# hydrogen_sensors_board_v3.net
KiCad netlist of a schematic drawn in EAGLE
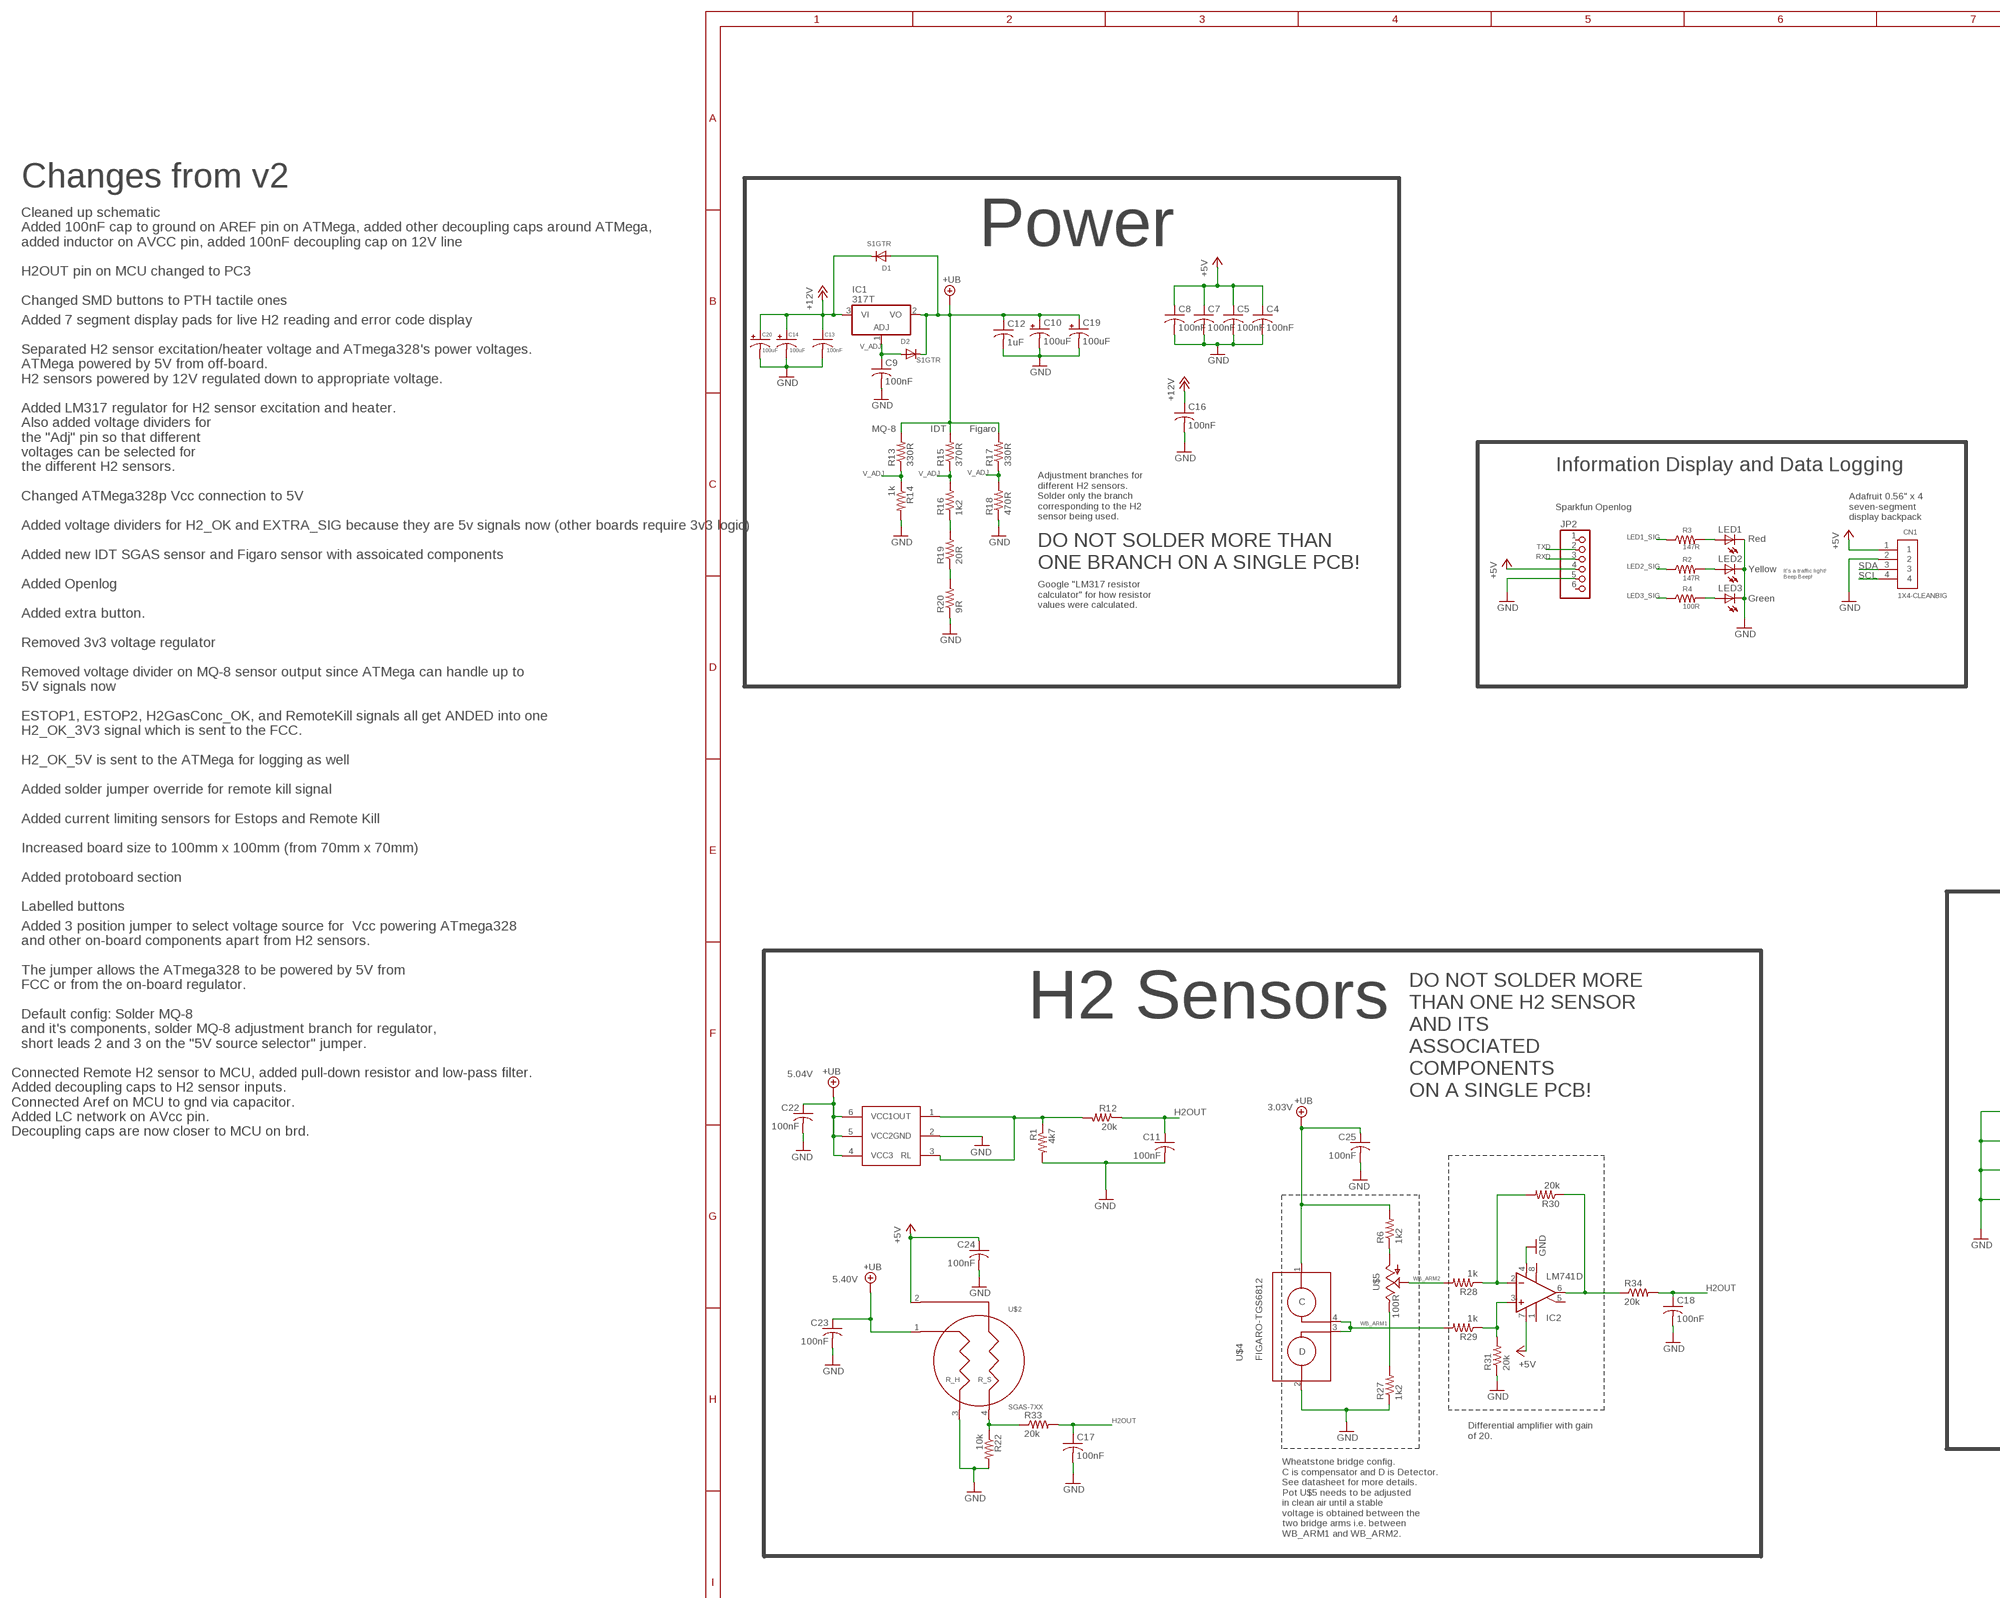
[diagram p0: schematic, sheet 1, part 1 of 2]
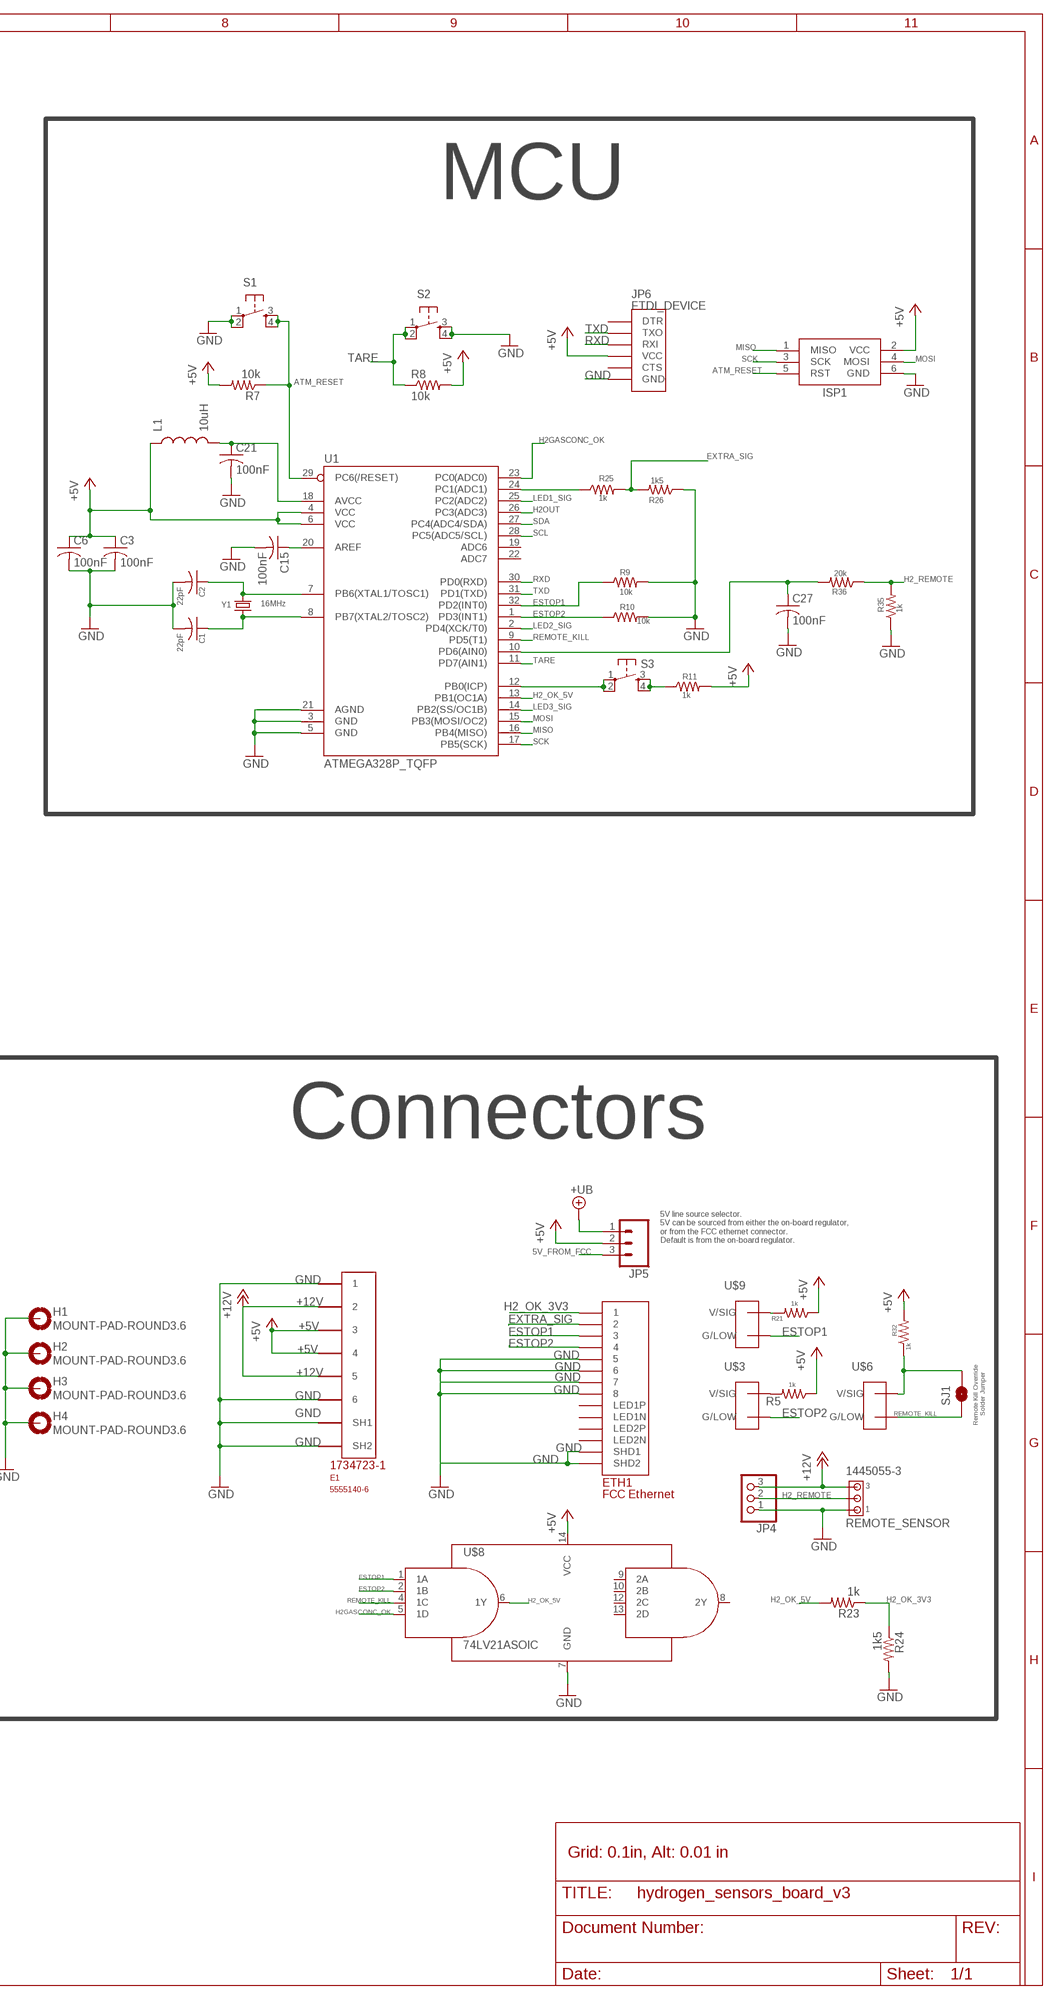
[diagram p1: schematic, sheet 1, part 2 of 2]

(export (version "E")
  (design (tool "Eeschema 10.0.6"))
  (components
    (comp (ref "C1")
      (value "22pF")
      (footprint "eagle-import:C0603K")
      (libsource (lib "eagle-import") (part "C-USC0603K"))
    )
    (comp (ref "C2")
      (value "22pF")
      (footprint "eagle-import:C0603K")
      (libsource (lib "eagle-import") (part "C-USC0603K"))
    )
    (comp (ref "C3")
      (value "100nF")
      (footprint "eagle-import:C0603")
      (libsource (lib "eagle-import") (part "C-USC0603"))
    )
    (comp (ref "C4")
      (value "100nF")
      (footprint "eagle-import:C0603")
      (libsource (lib "eagle-import") (part "C-USC0603"))
    )
    (comp (ref "C5")
      (value "100nF")
      (footprint "eagle-import:C0603")
      (libsource (lib "eagle-import") (part "C-USC0603"))
    )
    (comp (ref "C6")
      (value "100nF")
      (footprint "eagle-import:C0603")
      (libsource (lib "eagle-import") (part "C-USC0603"))
    )
    (comp (ref "C7")
      (value "100nF")
      (footprint "eagle-import:C0603")
      (libsource (lib "eagle-import") (part "C-USC0603"))
    )
    (comp (ref "C8")
      (value "100nF")
      (footprint "eagle-import:C0603")
      (libsource (lib "eagle-import") (part "C-USC0603"))
    )
    (comp (ref "C9")
      (value "100nF")
      (footprint "eagle-import:C0603")
      (libsource (lib "eagle-import") (part "C-USC0603"))
    )
    (comp (ref "C10")
      (value "100uF")
      (footprint "eagle-import:B_3528-21R")
      (libsource (lib "eagle-import") (part "CPOL-USB/3528-21R"))
    )
    (comp (ref "C11")
      (value "100nF")
      (footprint "eagle-import:C0603")
      (libsource (lib "eagle-import") (part "C-USC0603"))
    )
    (comp (ref "C12")
      (value "1uF")
      (footprint "eagle-import:C0603")
      (libsource (lib "eagle-import") (part "C-USC0603"))
    )
    (comp (ref "C13")
      (value "100nF")
      (footprint "eagle-import:C0603")
      (libsource (lib "eagle-import") (part "C-USC0603"))
    )
    (comp (ref "C14")
      (value "100uF")
      (footprint "eagle-import:B_3528-21R")
      (libsource (lib "eagle-import") (part "CPOL-USB/3528-21R"))
    )
    (comp (ref "C15")
      (value "100nF")
      (footprint "eagle-import:C0603")
      (libsource (lib "eagle-import") (part "C-USC0603"))
    )
    (comp (ref "C16")
      (value "100nF")
      (footprint "eagle-import:C0603")
      (libsource (lib "eagle-import") (part "C-USC0603"))
    )
    (comp (ref "C17")
      (value "100nF")
      (footprint "eagle-import:C0603")
      (libsource (lib "eagle-import") (part "C-USC0603"))
    )
    (comp (ref "C18")
      (value "100nF")
      (footprint "eagle-import:C0603")
      (libsource (lib "eagle-import") (part "C-USC0603"))
    )
    (comp (ref "C19")
      (value "100uF")
      (footprint "eagle-import:CPOL-RADIAL-100UF-25V")
      (libsource (lib "eagle-import") (part "CAP_POLPTH1"))
    )
    (comp (ref "C20")
      (value "100uF")
      (footprint "eagle-import:CPOL-RADIAL-100UF-25V")
      (libsource (lib "eagle-import") (part "CAP_POLPTH1"))
    )
    (comp (ref "C21")
      (value "100nF")
      (footprint "eagle-import:C0603")
      (libsource (lib "eagle-import") (part "C-USC0603"))
    )
    (comp (ref "C22")
      (value "100nF")
      (footprint "eagle-import:C0603")
      (libsource (lib "eagle-import") (part "C-USC0603"))
    )
    (comp (ref "C23")
      (value "100nF")
      (footprint "eagle-import:C0603")
      (libsource (lib "eagle-import") (part "C-USC0603"))
    )
    (comp (ref "C24")
      (value "100nF")
      (footprint "eagle-import:C0603")
      (libsource (lib "eagle-import") (part "C-USC0603"))
    )
    (comp (ref "C25")
      (value "100nF")
      (footprint "eagle-import:C0603")
      (libsource (lib "eagle-import") (part "C-USC0603"))
    )
    (comp (ref "C27")
      (value "100nF")
      (footprint "eagle-import:C0603")
      (libsource (lib "eagle-import") (part "C-USC0603"))
    )
    (comp (ref "CN1")
      (value "1X4-CLEANBIG")
      (footprint "eagle-import:1X04-CLEANBIG")
      (libsource (lib "eagle-import") (part "1X4-CLEANBIG"))
    )
    (comp (ref "D1")
      (value "S1GTR")
      (footprint "eagle-import:SMADIODE")
      (libsource (lib "eagle-import") (part "DIODESMA"))
    )
    (comp (ref "D2")
      (value "S1GTR")
      (footprint "eagle-import:SMADIODE")
      (libsource (lib "eagle-import") (part "DIODESMA"))
    )
    (comp (ref "E1")
      (value "5555140-6")
      (footprint "eagle-import:1734723-1_RJ11")
      (libsource (lib "eagle-import") (part "5555140-6"))
    )
    (comp (ref "ETH1")
      (value "FCC Ethernet")
      (footprint "eagle-import:A122645-ND")
      (libsource (lib "eagle-import") (part "ETHERNET"))
    )
    (comp (ref "H1")
      (value "MOUNT-PAD-ROUND3.6")
      (footprint "eagle-import:3,6-PAD")
      (libsource (lib "eagle-import") (part "MOUNT-PAD-ROUND3.6"))
    )
    (comp (ref "H2")
      (value "MOUNT-PAD-ROUND3.6")
      (footprint "eagle-import:3,6-PAD")
      (libsource (lib "eagle-import") (part "MOUNT-PAD-ROUND3.6"))
    )
    (comp (ref "H3")
      (value "MOUNT-PAD-ROUND3.6")
      (footprint "eagle-import:3,6-PAD")
      (libsource (lib "eagle-import") (part "MOUNT-PAD-ROUND3.6"))
    )
    (comp (ref "H4")
      (value "MOUNT-PAD-ROUND3.6")
      (footprint "eagle-import:3,6-PAD")
      (libsource (lib "eagle-import") (part "MOUNT-PAD-ROUND3.6"))
    )
    (comp (ref "IC1")
      (value "317T")
      (footprint "eagle-import:TO220H")
      (libsource (lib "eagle-import") (part "317T"))
    )
    (comp (ref "IC2")
      (value "LM741D")
      (footprint "eagle-import:SO08")
      (libsource (lib "eagle-import") (part "741DLM"))
    )
    (comp (ref "ISP1")
      (value "AVRISP-BOX")
      (footprint "eagle-import:AVRISP-BOX")
      (libsource (lib "eagle-import") (part "AVRISP-BOX"))
    )
    (comp (ref "JP2")
      (value "PINHD-1X6LOCK")
      (footprint "eagle-import:1X06-BIGLOCK")
      (libsource (lib "eagle-import") (part "PINHD-1X6LOCK"))
    )
    (comp (ref "JP4")
      (value "PINHD-1X3")
      (footprint "eagle-import:1X03")
      (libsource (lib "eagle-import") (part "PINHD-1X3"))
    )
    (comp (ref "JP5")
      (value "M03PTH")
      (footprint "eagle-import:1X03")
      (libsource (lib "eagle-import") (part "M03PTH"))
    )
    (comp (ref "JP6")
      (value "FTDI_DEVICE")
      (footprint "eagle-import:FTDI_DEVICE_SIDE")
      (libsource (lib "eagle-import") (part "FTDI_DEVICE"))
    )
    (comp (ref "L1")
      (value "10uH")
      (footprint "eagle-import:0603")
      (libsource (lib "eagle-import") (part "INDUCTOR0603"))
    )
    (comp (ref "LED1")
      (value "Red")
      (footprint "eagle-import:CHIPLED_0805")
      (libsource (lib "eagle-import") (part "LEDCHIPLED_0805"))
    )
    (comp (ref "LED2")
      (value "Yellow")
      (footprint "eagle-import:CHIPLED_0805")
      (libsource (lib "eagle-import") (part "LEDCHIPLED_0805"))
    )
    (comp (ref "LED3")
      (value "Green")
      (footprint "eagle-import:CHIPLED_0805")
      (libsource (lib "eagle-import") (part "LEDCHIPLED_0805"))
    )
    (comp (ref "R1")
      (value "4k7")
      (footprint "eagle-import:0603-RES")
      (libsource (lib "eagle-import") (part "RESISTOR0603-RES"))
    )
    (comp (ref "R2")
      (value "147R")
      (footprint "eagle-import:0603-RES")
      (libsource (lib "eagle-import") (part "SparkFun-Resistors_RESISTOR0603-RES"))
    )
    (comp (ref "R3")
      (value "147R")
      (footprint "eagle-import:0603-RES")
      (libsource (lib "eagle-import") (part "SparkFun-Resistors_RESISTOR0603-RES"))
    )
    (comp (ref "R4")
      (value "100R")
      (footprint "eagle-import:0603-RES")
      (libsource (lib "eagle-import") (part "SparkFun-Resistors_RESISTOR0603-RES"))
    )
    (comp (ref "R5")
      (value "1k")
      (footprint "eagle-import:0603-RES")
      (libsource (lib "eagle-import") (part "RESISTOR0603-RES"))
    )
    (comp (ref "R6")
      (value "1k2")
      (footprint "eagle-import:0603-RES")
      (libsource (lib "eagle-import") (part "RESISTOR0603-RES"))
    )
    (comp (ref "R7")
      (value "10k")
      (footprint "eagle-import:0603-RES")
      (libsource (lib "eagle-import") (part "SparkFun-Resistors_RESISTOR0603-RES"))
    )
    (comp (ref "R8")
      (value "10k")
      (footprint "eagle-import:0603-RES")
      (libsource (lib "eagle-import") (part "SparkFun-Resistors_RESISTOR0603-RES"))
    )
    (comp (ref "R9")
      (value "10k")
      (footprint "eagle-import:0603-RES")
      (libsource (lib "eagle-import") (part "RESISTOR0603-RES"))
    )
    (comp (ref "R10")
      (value "10k")
      (footprint "eagle-import:0603-RES")
      (libsource (lib "eagle-import") (part "RESISTOR0603-RES"))
    )
    (comp (ref "R11")
      (value "1k")
      (footprint "eagle-import:0603-RES")
      (libsource (lib "eagle-import") (part "RESISTOR0603-RES"))
    )
    (comp (ref "R12")
      (value "20k")
      (footprint "eagle-import:0603-RES")
      (libsource (lib "eagle-import") (part "RESISTOR0603-RES"))
    )
    (comp (ref "R13")
      (value "330R")
      (footprint "eagle-import:0603-RES")
      (libsource (lib "eagle-import") (part "SparkFun-Resistors_RESISTOR0603-RES"))
    )
    (comp (ref "R14")
      (value "1k")
      (footprint "eagle-import:0603-RES")
      (libsource (lib "eagle-import") (part "SparkFun-Resistors_RESISTOR0603-RES"))
    )
    (comp (ref "R15")
      (value "370R")
      (footprint "eagle-import:0603-RES")
      (libsource (lib "eagle-import") (part "SparkFun-Resistors_RESISTOR0603-RES"))
    )
    (comp (ref "R16")
      (value "1k2")
      (footprint "eagle-import:0603-RES")
      (libsource (lib "eagle-import") (part "SparkFun-Resistors_RESISTOR0603-RES"))
    )
    (comp (ref "R17")
      (value "330R")
      (footprint "eagle-import:0603-RES")
      (libsource (lib "eagle-import") (part "SparkFun-Resistors_RESISTOR0603-RES"))
    )
    (comp (ref "R18")
      (value "470R")
      (footprint "eagle-import:0603-RES")
      (libsource (lib "eagle-import") (part "SparkFun-Resistors_RESISTOR0603-RES"))
    )
    (comp (ref "R19")
      (value "20R")
      (footprint "eagle-import:0603-RES")
      (libsource (lib "eagle-import") (part "SparkFun-Resistors_RESISTOR0603-RES"))
    )
    (comp (ref "R20")
      (value "9R")
      (footprint "eagle-import:0603-RES")
      (libsource (lib "eagle-import") (part "SparkFun-Resistors_RESISTOR0603-RES"))
    )
    (comp (ref "R21")
      (value "1k")
      (footprint "eagle-import:0603-RES")
      (libsource (lib "eagle-import") (part "RESISTOR0603-RES"))
    )
    (comp (ref "R22")
      (value "10k")
      (footprint "eagle-import:0603-RES")
      (libsource (lib "eagle-import") (part "RESISTOR0603-RES"))
    )
    (comp (ref "R23")
      (value "1k")
      (footprint "eagle-import:0603-RES")
      (libsource (lib "eagle-import") (part "RESISTOR0603-RES"))
    )
    (comp (ref "R24")
      (value "1k5")
      (footprint "eagle-import:0603-RES")
      (libsource (lib "eagle-import") (part "RESISTOR0603-RES"))
    )
    (comp (ref "R25")
      (value "1k")
      (footprint "eagle-import:0603-RES")
      (libsource (lib "eagle-import") (part "SparkFun-Resistors_RESISTOR0603-RES"))
    )
    (comp (ref "R26")
      (value "1k5")
      (footprint "eagle-import:0603-RES")
      (libsource (lib "eagle-import") (part "SparkFun-Resistors_RESISTOR0603-RES"))
    )
    (comp (ref "R27")
      (value "1k2")
      (footprint "eagle-import:0603-RES")
      (libsource (lib "eagle-import") (part "RESISTOR0603-RES"))
    )
    (comp (ref "R28")
      (value "1k")
      (footprint "eagle-import:0603-RES")
      (libsource (lib "eagle-import") (part "RESISTOR0603-RES"))
    )
    (comp (ref "R29")
      (value "1k")
      (footprint "eagle-import:0603-RES")
      (libsource (lib "eagle-import") (part "RESISTOR0603-RES"))
    )
    (comp (ref "R30")
      (value "20k")
      (footprint "eagle-import:0603-RES")
      (libsource (lib "eagle-import") (part "RESISTOR0603-RES"))
    )
    (comp (ref "R31")
      (value "20k")
      (footprint "eagle-import:0603-RES")
      (libsource (lib "eagle-import") (part "RESISTOR0603-RES"))
    )
    (comp (ref "R32")
      (value "1k")
      (footprint "eagle-import:0603-RES")
      (libsource (lib "eagle-import") (part "RESISTOR0603-RES"))
    )
    (comp (ref "R33")
      (value "20k")
      (footprint "eagle-import:0603-RES")
      (libsource (lib "eagle-import") (part "RESISTOR0603-RES"))
    )
    (comp (ref "R34")
      (value "20k")
      (footprint "eagle-import:0603-RES")
      (libsource (lib "eagle-import") (part "RESISTOR0603-RES"))
    )
    (comp (ref "R35")
      (value "1k")
      (footprint "eagle-import:0603-RES")
      (libsource (lib "eagle-import") (part "RESISTOR0603-RES"))
    )
    (comp (ref "R36")
      (value "20k")
      (footprint "eagle-import:0603-RES")
      (libsource (lib "eagle-import") (part "RESISTOR0603-RES"))
    )
    (comp (ref "REMOTE_SENSOR")
      (value "1445055-3")
      (footprint "eagle-import:1445055-3")
      (libsource (lib "eagle-import") (part "1445055-3"))
    )
    (comp (ref "S1")
      (value "TAC_SWITCHPTH")
      (footprint "eagle-import:TACTILE-PTH")
      (libsource (lib "eagle-import") (part "TAC_SWITCHPTH"))
    )
    (comp (ref "S2")
      (value "TAC_SWITCHPTH")
      (footprint "eagle-import:TACTILE-PTH")
      (libsource (lib "eagle-import") (part "TAC_SWITCHPTH"))
    )
    (comp (ref "S3")
      (value "TAC_SWITCHPTH")
      (footprint "eagle-import:TACTILE-PTH")
      (libsource (lib "eagle-import") (part "TAC_SWITCHPTH"))
    )
    (comp (ref "SJ1")
      (value "SOLDERJUMPERNO")
      (footprint "eagle-import:SJ_2S-NO")
      (libsource (lib "eagle-import") (part "SOLDERJUMPERNO"))
    )
    (comp (ref "U$1")
      (value "MQ-8MQ-8")
      (footprint "eagle-import:MQ-8")
      (libsource (lib "eagle-import") (part "MQ-8MQ-8"))
    )
    (comp (ref "U$2")
      (value "SGAS-7XX")
      (footprint "eagle-import:TO39")
      (libsource (lib "eagle-import") (part "SGAS-7XX"))
    )
    (comp (ref "U$3")
      (value "TE770966")
      (footprint "eagle-import:2X1-MATE-N-LOCK")
      (libsource (lib "eagle-import") (part "TE770966"))
    )
    (comp (ref "U$4")
      (value "FIGARO-TGS6812")
      (footprint "eagle-import:4PTH")
      (libsource (lib "eagle-import") (part "FIGARO-TGS6812"))
    )
    (comp (ref "U$5")
      (value "100R")
      (footprint "eagle-import:3362U")
      (libsource (lib "eagle-import") (part "POT100K_3362U"))
    )
    (comp (ref "U$6")
      (value "TE770966")
      (footprint "eagle-import:2X1-MATE-N-LOCK")
      (libsource (lib "eagle-import") (part "TE770966"))
    )
    (comp (ref "U$8")
      (value "74LV21ASOIC")
      (footprint "eagle-import:SOIC-14")
      (libsource (lib "eagle-import") (part "74LV21ASOIC"))
    )
    (comp (ref "U$9")
      (value "TE770966")
      (footprint "eagle-import:2X1-MATE-N-LOCK")
      (libsource (lib "eagle-import") (part "TE770966"))
    )
    (comp (ref "U1")
      (value "ATMEGA328P_TQFP")
      (footprint "eagle-import:TQFP32-08")
      (libsource (lib "eagle-import") (part "ATMEGA328P_TQFP"))
    )
    (comp (ref "Y1")
      (value "16MHz")
      (footprint "eagle-import:HC49US")
      (libsource (lib "eagle-import") (part "CRYSTALHC49US"))
    )
  )
  (nets
    (net (code "1") (name "+5V") (class "Default")
      (node (ref "C24") (pin "1") (pinfunction "1_1") (pintype "passive"))
      (node (ref "C3") (pin "1") (pinfunction "1_1") (pintype "passive"))
      (node (ref "C4") (pin "1") (pinfunction "1_1") (pintype "passive"))
      (node (ref "C5") (pin "1") (pinfunction "1_1") (pintype "passive"))
      (node (ref "C6") (pin "1") (pinfunction "1_1") (pintype "passive"))
      (node (ref "C7") (pin "1") (pinfunction "1_1") (pintype "passive"))
      (node (ref "C8") (pin "1") (pinfunction "1_1") (pintype "passive"))
      (node (ref "CN1") (pin "1") (pinfunction "1_1") (pintype "bidirectional"))
      (node (ref "E1") (pin "3") (pinfunction "3_3") (pintype "bidirectional"))
      (node (ref "E1") (pin "4") (pinfunction "4_4") (pintype "bidirectional"))
      (node (ref "IC2") (pin "7") (pinfunction "V+_7") (pintype "power_in"))
      (node (ref "ISP1") (pin "2") (pinfunction "VCC_2") (pintype "power_in"))
      (node (ref "JP2") (pin "4") (pinfunction "4_4") (pintype "passive"))
      (node (ref "JP5") (pin "2") (pinfunction "2_2") (pintype "passive"))
      (node (ref "JP6") (pin "P$4") (pinfunction "VCC_P$4") (pintype "bidirectional"))
      (node (ref "L1") (pin "1") (pinfunction "1_1") (pintype "passive"))
      (node (ref "R11") (pin "2") (pinfunction "2_2") (pintype "passive"))
      (node (ref "R21") (pin "1") (pinfunction "1_1") (pintype "passive"))
      (node (ref "R32") (pin "2") (pinfunction "2_2") (pintype "passive"))
      (node (ref "R5") (pin "1") (pinfunction "1_1") (pintype "passive"))
      (node (ref "R7") (pin "2") (pinfunction "2_2") (pintype "passive"))
      (node (ref "R8") (pin "2") (pinfunction "2_2") (pintype "passive"))
      (node (ref "U$2") (pin "2") (pinfunction "2_2") (pintype "bidirectional"))
      (node (ref "U$8") (pin "14") (pinfunction "VCC_14") (pintype "power_in"))
      (node (ref "U1") (pin "4") (pinfunction "VCC_4") (pintype "bidirectional"))
      (node (ref "U1") (pin "6") (pinfunction "VCC_6") (pintype "bidirectional"))
    )
    (net (code "2") (name "+12V") (class "Default")
      (node (ref "C13") (pin "1") (pinfunction "1_1") (pintype "passive"))
      (node (ref "C14") (pin "+") (pinfunction "+_+") (pintype "passive"))
      (node (ref "C16") (pin "1") (pinfunction "1_1") (pintype "passive"))
      (node (ref "C20") (pin "1") (pinfunction "+_1") (pintype "passive"))
      (node (ref "D1") (pin "C") (pinfunction "C_C") (pintype "passive"))
      (node (ref "E1") (pin "2") (pinfunction "2_2") (pintype "bidirectional"))
      (node (ref "E1") (pin "5") (pinfunction "5_5") (pintype "bidirectional"))
      (node (ref "IC1") (pin "3") (pinfunction "VI_3") (pintype "input"))
      (node (ref "JP4") (pin "3") (pinfunction "3_3") (pintype "passive"))
      (node (ref "REMOTE_SENSOR") (pin "3") (pinfunction "3_3") (pintype "passive"))
    )
    (net (code "3") (name "+UB") (class "Default")
      (node (ref "C10") (pin "+") (pinfunction "+_+") (pintype "passive"))
      (node (ref "C12") (pin "1") (pinfunction "1_1") (pintype "passive"))
      (node (ref "C19") (pin "1") (pinfunction "+_1") (pintype "passive"))
      (node (ref "C22") (pin "1") (pinfunction "1_1") (pintype "passive"))
      (node (ref "C23") (pin "1") (pinfunction "1_1") (pintype "passive"))
      (node (ref "C25") (pin "1") (pinfunction "1_1") (pintype "passive"))
      (node (ref "D1") (pin "A") (pinfunction "A_A") (pintype "passive"))
      (node (ref "D2") (pin "C") (pinfunction "C_C") (pintype "passive"))
      (node (ref "IC1") (pin "2") (pinfunction "VO_2") (pintype "passive"))
      (node (ref "JP5") (pin "1") (pinfunction "1_1") (pintype "passive"))
      (node (ref "R13") (pin "2") (pinfunction "2_2") (pintype "passive"))
      (node (ref "R15") (pin "2") (pinfunction "2_2") (pintype "passive"))
      (node (ref "R17") (pin "2") (pinfunction "2_2") (pintype "passive"))
      (node (ref "R6") (pin "2") (pinfunction "2_2") (pintype "passive"))
      (node (ref "U$1") (pin "4") (pinfunction "VCC3_4") (pintype "bidirectional"))
      (node (ref "U$1") (pin "5") (pinfunction "VCC2_5") (pintype "bidirectional"))
      (node (ref "U$1") (pin "6") (pinfunction "VCC1_6") (pintype "bidirectional"))
      (node (ref "U$2") (pin "1") (pinfunction "1_1") (pintype "bidirectional"))
      (node (ref "U$4") (pin "1") (pinfunction "1_1") (pintype "bidirectional"))
    )
    (net (code "4") (name "/5V_FROM_FCC") (class "Default")
      (node (ref "JP5") (pin "3") (pinfunction "3_3") (pintype "passive"))
    )
    (net (code "5") (name "/ATM_RESET") (class "Default")
      (node (ref "ISP1") (pin "5") (pinfunction "RST_5") (pintype "output"))
      (node (ref "R7") (pin "1") (pinfunction "1_1") (pintype "passive"))
      (node (ref "S1") (pin "3") (pinfunction "3_3") (pintype "passive"))
      (node (ref "S1") (pin "4") (pinfunction "4_4") (pintype "passive"))
      (node (ref "U1") (pin "29") (pinfunction "PC6(/RESET)_29") (pintype "bidirectional"))
    )
    (net (code "6") (name "/ESTOP1") (class "Default")
      (node (ref "ETH1") (pin "P$3") (pinfunction "3_P$3") (pintype "bidirectional"))
      (node (ref "R9") (pin "1") (pinfunction "1_1") (pintype "passive"))
      (node (ref "U$8") (pin "1") (pinfunction "1A_1") (pintype "bidirectional"))
      (node (ref "U$9") (pin "CIRCUIT2") (pinfunction "G/LOW_CIRCUIT2") (pintype "bidirectional"))
      (node (ref "U1") (pin "32") (pinfunction "PD2(INT0)_32") (pintype "bidirectional"))
    )
    (net (code "7") (name "/ESTOP2") (class "Default")
      (node (ref "ETH1") (pin "P$4") (pinfunction "4_P$4") (pintype "bidirectional"))
      (node (ref "R10") (pin "1") (pinfunction "1_1") (pintype "passive"))
      (node (ref "U$3") (pin "CIRCUIT2") (pinfunction "G/LOW_CIRCUIT2") (pintype "bidirectional"))
      (node (ref "U$8") (pin "2") (pinfunction "1B_2") (pintype "bidirectional"))
      (node (ref "U1") (pin "1") (pinfunction "PD3(INT1)_1") (pintype "bidirectional"))
    )
    (net (code "8") (name "/EXTRA_SIG") (class "Default")
      (node (ref "ETH1") (pin "P$2") (pinfunction "2_P$2") (pintype "bidirectional"))
      (node (ref "R25") (pin "2") (pinfunction "2_2") (pintype "passive"))
      (node (ref "R26") (pin "2") (pinfunction "2_2") (pintype "passive"))
    )
    (net (code "9") (name "/H2GASCONC_OK") (class "Default")
      (node (ref "U$8") (pin "5") (pinfunction "1D_5") (pintype "bidirectional"))
      (node (ref "U1") (pin "23") (pinfunction "PC0(ADC0)_23") (pintype "bidirectional"))
    )
    (net (code "10") (name "/H2OUT") (class "Default")
      (node (ref "C11") (pin "1") (pinfunction "1_1") (pintype "passive"))
      (node (ref "C17") (pin "1") (pinfunction "1_1") (pintype "passive"))
      (node (ref "C18") (pin "1") (pinfunction "1_1") (pintype "passive"))
      (node (ref "R12") (pin "1") (pinfunction "1_1") (pintype "passive"))
      (node (ref "R33") (pin "2") (pinfunction "2_2") (pintype "passive"))
      (node (ref "R34") (pin "2") (pinfunction "2_2") (pintype "passive"))
      (node (ref "U1") (pin "26") (pinfunction "PC3(ADC3)_26") (pintype "bidirectional"))
    )
    (net (code "11") (name "/H2_OK_3V3") (class "Default")
      (node (ref "ETH1") (pin "P$1") (pinfunction "1_P$1") (pintype "bidirectional"))
      (node (ref "R23") (pin "1") (pinfunction "1_1") (pintype "passive"))
      (node (ref "R24") (pin "1") (pinfunction "1_1") (pintype "passive"))
    )
    (net (code "12") (name "/H2_OK_5V") (class "Default")
      (node (ref "R23") (pin "2") (pinfunction "2_2") (pintype "passive"))
      (node (ref "U$8") (pin "6") (pinfunction "1Y_6") (pintype "bidirectional"))
      (node (ref "U1") (pin "13") (pinfunction "PB1(OC1A)_13") (pintype "bidirectional"))
    )
    (net (code "13") (name "/H2_REMOTE") (class "Default")
      (node (ref "JP4") (pin "2") (pinfunction "2_2") (pintype "passive"))
      (node (ref "R35") (pin "2") (pinfunction "2_2") (pintype "passive"))
      (node (ref "R36") (pin "1") (pinfunction "1_1") (pintype "passive"))
      (node (ref "REMOTE_SENSOR") (pin "2") (pinfunction "2_2") (pintype "passive"))
    )
    (net (code "14") (name "/LED1_SIG") (class "Default")
      (node (ref "R3") (pin "1") (pinfunction "1_1") (pintype "passive"))
      (node (ref "U1") (pin "25") (pinfunction "PC2(ADC2)_25") (pintype "bidirectional"))
    )
    (net (code "15") (name "/LED2_SIG") (class "Default")
      (node (ref "R2") (pin "1") (pinfunction "1_1") (pintype "passive"))
      (node (ref "U1") (pin "2") (pinfunction "PD4(XCK/T0)_2") (pintype "bidirectional"))
    )
    (net (code "16") (name "/LED3_SIG") (class "Default")
      (node (ref "R4") (pin "1") (pinfunction "1_1") (pintype "passive"))
      (node (ref "U1") (pin "14") (pinfunction "PB2(SS/OC1B)_14") (pintype "bidirectional"))
    )
    (net (code "17") (name "/MISO") (class "Default")
      (node (ref "ISP1") (pin "1") (pinfunction "MISO_1") (pintype "input"))
      (node (ref "U1") (pin "16") (pinfunction "PB4(MISO)_16") (pintype "bidirectional"))
    )
    (net (code "18") (name "/MOSI") (class "Default")
      (node (ref "ISP1") (pin "4") (pinfunction "MOSI_4") (pintype "output"))
      (node (ref "U1") (pin "15") (pinfunction "PB3(MOSI/OC2)_15") (pintype "bidirectional"))
    )
    (net (code "19") (name "/REMOTE_KILL") (class "Default")
      (node (ref "SJ1") (pin "1") (pinfunction "1_1") (pintype "passive"))
      (node (ref "U$6") (pin "CIRCUIT2") (pinfunction "G/LOW_CIRCUIT2") (pintype "bidirectional"))
      (node (ref "U$8") (pin "4") (pinfunction "1C_4") (pintype "bidirectional"))
      (node (ref "U1") (pin "9") (pinfunction "PD5(T1)_9") (pintype "bidirectional"))
    )
    (net (code "20") (name "/RXD") (class "Default")
      (node (ref "JP2") (pin "3") (pinfunction "3_3") (pintype "passive"))
      (node (ref "JP6") (pin "P$3") (pinfunction "RXI_P$3") (pintype "bidirectional"))
      (node (ref "U1") (pin "30") (pinfunction "PD0(RXD)_30") (pintype "bidirectional"))
    )
    (net (code "21") (name "/SCK") (class "Default")
      (node (ref "ISP1") (pin "3") (pinfunction "SCK_3") (pintype "output"))
      (node (ref "U1") (pin "17") (pinfunction "PB5(SCK)_17") (pintype "bidirectional"))
    )
    (net (code "22") (name "/SCL") (class "Default")
      (node (ref "CN1") (pin "4") (pinfunction "4_4") (pintype "bidirectional"))
      (node (ref "U1") (pin "28") (pinfunction "PC5(ADC5/SCL)_28") (pintype "bidirectional"))
    )
    (net (code "23") (name "/SDA") (class "Default")
      (node (ref "CN1") (pin "3") (pinfunction "3_3") (pintype "bidirectional"))
      (node (ref "U1") (pin "27") (pinfunction "PC4(ADC4/SDA)_27") (pintype "bidirectional"))
    )
    (net (code "24") (name "/TARE") (class "Default")
      (node (ref "R8") (pin "1") (pinfunction "1_1") (pintype "passive"))
      (node (ref "S2") (pin "1") (pinfunction "1_1") (pintype "passive"))
      (node (ref "S2") (pin "2") (pinfunction "2_2") (pintype "passive"))
      (node (ref "U1") (pin "11") (pinfunction "PD7(AIN1)_11") (pintype "bidirectional"))
    )
    (net (code "25") (name "/TXD") (class "Default")
      (node (ref "JP2") (pin "2") (pinfunction "2_2") (pintype "passive"))
      (node (ref "JP6") (pin "P$2") (pinfunction "TXO_P$2") (pintype "bidirectional"))
      (node (ref "U1") (pin "31") (pinfunction "PD1(TXD)_31") (pintype "bidirectional"))
    )
    (net (code "26") (name "/V_ADJ") (class "Default")
      (node (ref "C9") (pin "1") (pinfunction "1_1") (pintype "passive"))
      (node (ref "D2") (pin "A") (pinfunction "A_A") (pintype "passive"))
      (node (ref "IC1") (pin "1") (pinfunction "ADJ_1") (pintype "input"))
      (node (ref "R13") (pin "1") (pinfunction "1_1") (pintype "passive"))
      (node (ref "R14") (pin "1") (pinfunction "1_1") (pintype "passive"))
      (node (ref "R15") (pin "1") (pinfunction "1_1") (pintype "passive"))
      (node (ref "R16") (pin "2") (pinfunction "2_2") (pintype "passive"))
      (node (ref "R17") (pin "1") (pinfunction "1_1") (pintype "passive"))
      (node (ref "R18") (pin "2") (pinfunction "2_2") (pintype "passive"))
    )
    (net (code "27") (name "/WB_ARM1") (class "Default")
      (node (ref "R29") (pin "2") (pinfunction "2_2") (pintype "passive"))
      (node (ref "U$4") (pin "3") (pinfunction "3_3") (pintype "bidirectional"))
      (node (ref "U$4") (pin "4") (pinfunction "4_4") (pintype "bidirectional"))
    )
    (net (code "28") (name "/WB_ARM2") (class "Default")
      (node (ref "R28") (pin "2") (pinfunction "2_2") (pintype "passive"))
      (node (ref "U$5") (pin "P$2") (pinfunction "S_P$2") (pintype "passive"))
    )
    (net (code "29") (name "GND") (class "Default")
      (node (ref "C1") (pin "2") (pinfunction "2_2") (pintype "passive"))
      (node (ref "C10") (pin "-") (pinfunction "-_-") (pintype "passive"))
      (node (ref "C11") (pin "2") (pinfunction "2_2") (pintype "passive"))
      (node (ref "C12") (pin "2") (pinfunction "2_2") (pintype "passive"))
      (node (ref "C13") (pin "2") (pinfunction "2_2") (pintype "passive"))
      (node (ref "C14") (pin "-") (pinfunction "-_-") (pintype "passive"))
      (node (ref "C15") (pin "2") (pinfunction "2_2") (pintype "passive"))
      (node (ref "C16") (pin "2") (pinfunction "2_2") (pintype "passive"))
      (node (ref "C17") (pin "2") (pinfunction "2_2") (pintype "passive"))
      (node (ref "C18") (pin "2") (pinfunction "2_2") (pintype "passive"))
      (node (ref "C19") (pin "2") (pinfunction "-_2") (pintype "passive"))
      (node (ref "C2") (pin "2") (pinfunction "2_2") (pintype "passive"))
      (node (ref "C20") (pin "2") (pinfunction "-_2") (pintype "passive"))
      (node (ref "C21") (pin "2") (pinfunction "2_2") (pintype "passive"))
      (node (ref "C22") (pin "2") (pinfunction "2_2") (pintype "passive"))
      (node (ref "C23") (pin "2") (pinfunction "2_2") (pintype "passive"))
      (node (ref "C24") (pin "2") (pinfunction "2_2") (pintype "passive"))
      (node (ref "C25") (pin "2") (pinfunction "2_2") (pintype "passive"))
      (node (ref "C27") (pin "2") (pinfunction "2_2") (pintype "passive"))
      (node (ref "C3") (pin "2") (pinfunction "2_2") (pintype "passive"))
      (node (ref "C4") (pin "2") (pinfunction "2_2") (pintype "passive"))
      (node (ref "C5") (pin "2") (pinfunction "2_2") (pintype "passive"))
      (node (ref "C6") (pin "2") (pinfunction "2_2") (pintype "passive"))
      (node (ref "C7") (pin "2") (pinfunction "2_2") (pintype "passive"))
      (node (ref "C8") (pin "2") (pinfunction "2_2") (pintype "passive"))
      (node (ref "C9") (pin "2") (pinfunction "2_2") (pintype "passive"))
      (node (ref "CN1") (pin "2") (pinfunction "2_2") (pintype "bidirectional"))
      (node (ref "E1") (pin "1") (pinfunction "1_1") (pintype "bidirectional"))
      (node (ref "E1") (pin "6") (pinfunction "6_6") (pintype "bidirectional"))
      (node (ref "E1") (pin "SH1") (pinfunction "SH1_SH1") (pintype "bidirectional"))
      (node (ref "E1") (pin "SH2") (pinfunction "SH2_SH2") (pintype "bidirectional"))
      (node (ref "ETH1") (pin "P$13") (pinfunction "SHD1_P$13") (pintype "bidirectional"))
      (node (ref "ETH1") (pin "P$14") (pinfunction "SHD2_P$14") (pintype "bidirectional"))
      (node (ref "ETH1") (pin "P$5") (pinfunction "5_P$5") (pintype "bidirectional"))
      (node (ref "ETH1") (pin "P$6") (pinfunction "6_P$6") (pintype "bidirectional"))
      (node (ref "ETH1") (pin "P$7") (pinfunction "7_P$7") (pintype "bidirectional"))
      (node (ref "ETH1") (pin "P$8") (pinfunction "8_P$8") (pintype "bidirectional"))
      (node (ref "H1") (pin "B3,6") (pinfunction "MOUNT_B3,6") (pintype "passive"))
      (node (ref "H2") (pin "B3,6") (pinfunction "MOUNT_B3,6") (pintype "passive"))
      (node (ref "H3") (pin "B3,6") (pinfunction "MOUNT_B3,6") (pintype "passive"))
      (node (ref "H4") (pin "B3,6") (pinfunction "MOUNT_B3,6") (pintype "passive"))
      (node (ref "IC2") (pin "4") (pinfunction "V-_4") (pintype "power_in"))
      (node (ref "ISP1") (pin "6") (pinfunction "GND_6") (pintype "power_in"))
      (node (ref "JP2") (pin "5") (pinfunction "5_5") (pintype "passive"))
      (node (ref "JP4") (pin "1") (pinfunction "1_1") (pintype "passive"))
      (node (ref "JP6") (pin "P$6") (pinfunction "GND_P$6") (pintype "bidirectional"))
      (node (ref "LED1") (pin "C") (pinfunction "C_C") (pintype "passive"))
      (node (ref "LED2") (pin "C") (pinfunction "C_C") (pintype "passive"))
      (node (ref "LED3") (pin "C") (pinfunction "C_C") (pintype "passive"))
      (node (ref "R1") (pin "2") (pinfunction "2_2") (pintype "passive"))
      (node (ref "R10") (pin "2") (pinfunction "2_2") (pintype "passive"))
      (node (ref "R14") (pin "2") (pinfunction "2_2") (pintype "passive"))
      (node (ref "R18") (pin "1") (pinfunction "1_1") (pintype "passive"))
      (node (ref "R20") (pin "1") (pinfunction "1_1") (pintype "passive"))
      (node (ref "R22") (pin "2") (pinfunction "2_2") (pintype "passive"))
      (node (ref "R24") (pin "2") (pinfunction "2_2") (pintype "passive"))
      (node (ref "R26") (pin "1") (pinfunction "1_1") (pintype "passive"))
      (node (ref "R27") (pin "1") (pinfunction "1_1") (pintype "passive"))
      (node (ref "R31") (pin "1") (pinfunction "1_1") (pintype "passive"))
      (node (ref "R35") (pin "1") (pinfunction "1_1") (pintype "passive"))
      (node (ref "R9") (pin "2") (pinfunction "2_2") (pintype "passive"))
      (node (ref "REMOTE_SENSOR") (pin "1") (pinfunction "1_1") (pintype "passive"))
      (node (ref "S1") (pin "1") (pinfunction "1_1") (pintype "passive"))
      (node (ref "S1") (pin "2") (pinfunction "2_2") (pintype "passive"))
      (node (ref "S2") (pin "3") (pinfunction "3_3") (pintype "passive"))
      (node (ref "S2") (pin "4") (pinfunction "4_4") (pintype "passive"))
      (node (ref "U$1") (pin "2") (pinfunction "GND_2") (pintype "bidirectional"))
      (node (ref "U$2") (pin "3") (pinfunction "3_3") (pintype "bidirectional"))
      (node (ref "U$4") (pin "2") (pinfunction "2_2") (pintype "bidirectional"))
      (node (ref "U$8") (pin "7") (pinfunction "GND_7") (pintype "power_in"))
      (node (ref "U1") (pin "21") (pinfunction "AGND_21") (pintype "bidirectional"))
      (node (ref "U1") (pin "3") (pinfunction "GND_3") (pintype "bidirectional"))
      (node (ref "U1") (pin "5") (pinfunction "GND_5") (pintype "bidirectional"))
    )
    (net (code "30") (name "Net-(IC2-+IN)") (class "Default")
      (node (ref "IC2") (pin "3") (pinfunction "+IN_3") (pintype "input"))
      (node (ref "R29") (pin "1") (pinfunction "1_1") (pintype "passive"))
      (node (ref "R31") (pin "2") (pinfunction "2_2") (pintype "passive"))
    )
    (net (code "31") (name "Net-(IC2--IN)") (class "Default")
      (node (ref "IC2") (pin "2") (pinfunction "-IN_2") (pintype "input"))
      (node (ref "R28") (pin "1") (pinfunction "1_1") (pintype "passive"))
      (node (ref "R30") (pin "2") (pinfunction "2_2") (pintype "passive"))
    )
    (net (code "32") (name "Net-(IC2-OUT)") (class "Default")
      (node (ref "IC2") (pin "6") (pinfunction "OUT_6") (pintype "output"))
      (node (ref "R30") (pin "1") (pinfunction "1_1") (pintype "passive"))
      (node (ref "R34") (pin "1") (pinfunction "1_1") (pintype "passive"))
    )
    (net (code "33") (name "Net-(LED1-PadA)") (class "Default")
      (node (ref "LED1") (pin "A") (pinfunction "A_A") (pintype "passive"))
      (node (ref "R3") (pin "2") (pinfunction "2_2") (pintype "passive"))
    )
    (net (code "34") (name "Net-(LED2-PadA)") (class "Default")
      (node (ref "LED2") (pin "A") (pinfunction "A_A") (pintype "passive"))
      (node (ref "R2") (pin "2") (pinfunction "2_2") (pintype "passive"))
    )
    (net (code "35") (name "Net-(LED3-PadA)") (class "Default")
      (node (ref "LED3") (pin "A") (pinfunction "A_A") (pintype "passive"))
      (node (ref "R4") (pin "2") (pinfunction "2_2") (pintype "passive"))
    )
    (net (code "36") (name "Net-(R11-Pad1)") (class "Default")
      (node (ref "R11") (pin "1") (pinfunction "1_1") (pintype "passive"))
      (node (ref "S3") (pin "3") (pinfunction "3_3") (pintype "passive"))
      (node (ref "S3") (pin "4") (pinfunction "4_4") (pintype "passive"))
    )
    (net (code "37") (name "Net-(R16-Pad1)") (class "Default")
      (node (ref "R16") (pin "1") (pinfunction "1_1") (pintype "passive"))
      (node (ref "R19") (pin "2") (pinfunction "2_2") (pintype "passive"))
    )
    (net (code "38") (name "Net-(R19-Pad1)") (class "Default")
      (node (ref "R19") (pin "1") (pinfunction "1_1") (pintype "passive"))
      (node (ref "R20") (pin "2") (pinfunction "2_2") (pintype "passive"))
    )
    (net (code "39") (name "Net-(R22-Pad1)") (class "Default")
      (node (ref "R22") (pin "1") (pinfunction "1_1") (pintype "passive"))
      (node (ref "R33") (pin "1") (pinfunction "1_1") (pintype "passive"))
      (node (ref "U$2") (pin "4") (pinfunction "4_4") (pintype "bidirectional"))
    )
    (net (code "40") (name "Net-(U$1-OUT)") (class "Default")
      (node (ref "R1") (pin "1") (pinfunction "1_1") (pintype "passive"))
      (node (ref "R12") (pin "2") (pinfunction "2_2") (pintype "passive"))
      (node (ref "U$1") (pin "1") (pinfunction "OUT_1") (pintype "bidirectional"))
      (node (ref "U$1") (pin "3") (pinfunction "RL_3") (pintype "bidirectional"))
    )
    (net (code "41") (name "Net-(U$3-V{slash}SIG)") (class "Default")
      (node (ref "R5") (pin "2") (pinfunction "2_2") (pintype "passive"))
      (node (ref "U$3") (pin "CIRCUIT1") (pinfunction "V/SIG_CIRCUIT1") (pintype "bidirectional"))
    )
    (net (code "42") (name "Net-(U$5-A)") (class "Default")
      (node (ref "R6") (pin "1") (pinfunction "1_1") (pintype "passive"))
      (node (ref "U$5") (pin "P$3") (pinfunction "A_P$3") (pintype "passive"))
    )
    (net (code "43") (name "Net-(U$5-E)") (class "Default")
      (node (ref "R27") (pin "2") (pinfunction "2_2") (pintype "passive"))
      (node (ref "U$5") (pin "P$1") (pinfunction "E_P$1") (pintype "passive"))
    )
    (net (code "44") (name "Net-(U$6-V{slash}SIG)") (class "Default")
      (node (ref "R32") (pin "1") (pinfunction "1_1") (pintype "passive"))
      (node (ref "SJ1") (pin "2") (pinfunction "2_2") (pintype "passive"))
      (node (ref "U$6") (pin "CIRCUIT1") (pinfunction "V/SIG_CIRCUIT1") (pintype "bidirectional"))
    )
    (net (code "45") (name "Net-(U$9-V{slash}SIG)") (class "Default")
      (node (ref "R21") (pin "2") (pinfunction "2_2") (pintype "passive"))
      (node (ref "U$9") (pin "CIRCUIT1") (pinfunction "V/SIG_CIRCUIT1") (pintype "bidirectional"))
    )
    (net (code "46") (name "Net-(U1-AREF)") (class "Default")
      (node (ref "C15") (pin "1") (pinfunction "1_1") (pintype "passive"))
      (node (ref "U1") (pin "20") (pinfunction "AREF_20") (pintype "bidirectional"))
    )
    (net (code "47") (name "Net-(U1-AVCC)") (class "Default")
      (node (ref "C21") (pin "1") (pinfunction "1_1") (pintype "passive"))
      (node (ref "L1") (pin "2") (pinfunction "2_2") (pintype "passive"))
      (node (ref "U1") (pin "18") (pinfunction "AVCC_18") (pintype "bidirectional"))
    )
    (net (code "48") (name "Net-(U1-PB0(ICP))") (class "Default")
      (node (ref "S3") (pin "1") (pinfunction "1_1") (pintype "passive"))
      (node (ref "S3") (pin "2") (pinfunction "2_2") (pintype "passive"))
      (node (ref "U1") (pin "12") (pinfunction "PB0(ICP)_12") (pintype "bidirectional"))
    )
    (net (code "49") (name "Net-(U1-PB6(XTAL1{slash}TOSC1))") (class "Default")
      (node (ref "C2") (pin "1") (pinfunction "1_1") (pintype "passive"))
      (node (ref "U1") (pin "7") (pinfunction "PB6(XTAL1/TOSC1)_7") (pintype "bidirectional"))
      (node (ref "Y1") (pin "2") (pinfunction "2_2") (pintype "passive"))
    )
    (net (code "50") (name "Net-(U1-PB7(XTAL2{slash}TOSC2))") (class "Default")
      (node (ref "C1") (pin "1") (pinfunction "1_1") (pintype "passive"))
      (node (ref "U1") (pin "8") (pinfunction "PB7(XTAL2/TOSC2)_8") (pintype "bidirectional"))
      (node (ref "Y1") (pin "1") (pinfunction "1_1") (pintype "passive"))
    )
    (net (code "51") (name "Net-(U1-PC1(ADC1))") (class "Default")
      (node (ref "R25") (pin "1") (pinfunction "1_1") (pintype "passive"))
      (node (ref "U1") (pin "24") (pinfunction "PC1(ADC1)_24") (pintype "bidirectional"))
    )
    (net (code "52") (name "Net-(U1-PD6(AIN0))") (class "Default")
      (node (ref "C27") (pin "1") (pinfunction "1_1") (pintype "passive"))
      (node (ref "R36") (pin "2") (pinfunction "2_2") (pintype "passive"))
      (node (ref "U1") (pin "10") (pinfunction "PD6(AIN0)_10") (pintype "bidirectional"))
    )
    (net (code "53") (name "unconnected-(ETH1-LED1N-PadP$9)") (class "Default")
      (node (ref "ETH1") (pin "P$9") (pinfunction "LED1N_P$9") (pintype "bidirectional"))
    )
    (net (code "54") (name "unconnected-(ETH1-LED1P-PadP$10)") (class "Default")
      (node (ref "ETH1") (pin "P$10") (pinfunction "LED1P_P$10") (pintype "bidirectional"))
    )
    (net (code "55") (name "unconnected-(ETH1-LED2N-PadP$11)") (class "Default")
      (node (ref "ETH1") (pin "P$11") (pinfunction "LED2N_P$11") (pintype "bidirectional"))
    )
    (net (code "56") (name "unconnected-(ETH1-LED2P-PadP$12)") (class "Default")
      (node (ref "ETH1") (pin "P$12") (pinfunction "LED2P_P$12") (pintype "bidirectional"))
    )
    (net (code "57") (name "unconnected-(IC2-ON1-Pad1)") (class "Default")
      (node (ref "IC2") (pin "1") (pinfunction "ON1_1") (pintype "passive"))
    )
    (net (code "58") (name "unconnected-(IC2-ON2-Pad5)") (class "Default")
      (node (ref "IC2") (pin "5") (pinfunction "ON2_5") (pintype "passive"))
    )
    (net (code "59") (name "unconnected-(IC2-OPT-Pad8)") (class "Default")
      (node (ref "IC2") (pin "8") (pinfunction "OPT_8") (pintype "passive"))
    )
    (net (code "60") (name "unconnected-(JP2-Pad1)") (class "Default")
      (node (ref "JP2") (pin "1") (pinfunction "1_1") (pintype "passive"))
    )
    (net (code "61") (name "unconnected-(JP2-Pad6)") (class "Default")
      (node (ref "JP2") (pin "6") (pinfunction "6_6") (pintype "passive"))
    )
    (net (code "62") (name "unconnected-(JP6-CTS-PadP$5)") (class "Default")
      (node (ref "JP6") (pin "P$5") (pinfunction "CTS_P$5") (pintype "bidirectional"))
    )
    (net (code "63") (name "unconnected-(JP6-DTR-PadP$1)") (class "Default")
      (node (ref "JP6") (pin "P$1") (pinfunction "DTR_P$1") (pintype "bidirectional"))
    )
    (net (code "64") (name "unconnected-(U$8-2A-Pad9)") (class "Default")
      (node (ref "U$8") (pin "9") (pinfunction "2A_9") (pintype "bidirectional"))
    )
    (net (code "65") (name "unconnected-(U$8-2B-Pad10)") (class "Default")
      (node (ref "U$8") (pin "10") (pinfunction "2B_10") (pintype "bidirectional"))
    )
    (net (code "66") (name "unconnected-(U$8-2C-Pad12)") (class "Default")
      (node (ref "U$8") (pin "12") (pinfunction "2C_12") (pintype "bidirectional"))
    )
    (net (code "67") (name "unconnected-(U$8-2D-Pad13)") (class "Default")
      (node (ref "U$8") (pin "13") (pinfunction "2D_13") (pintype "bidirectional"))
    )
    (net (code "68") (name "unconnected-(U$8-2Y-Pad8)") (class "Default")
      (node (ref "U$8") (pin "8") (pinfunction "2Y_8") (pintype "bidirectional"))
    )
    (net (code "69") (name "unconnected-(U1-ADC6-Pad19)") (class "Default")
      (node (ref "U1") (pin "19") (pinfunction "ADC6_19") (pintype "bidirectional"))
    )
    (net (code "70") (name "unconnected-(U1-ADC7-Pad22)") (class "Default")
      (node (ref "U1") (pin "22") (pinfunction "ADC7_22") (pintype "bidirectional"))
    )
  )
)
